# 5_High_V_Sensor.net
KiCad netlist of a schematic drawn in Altium Designer
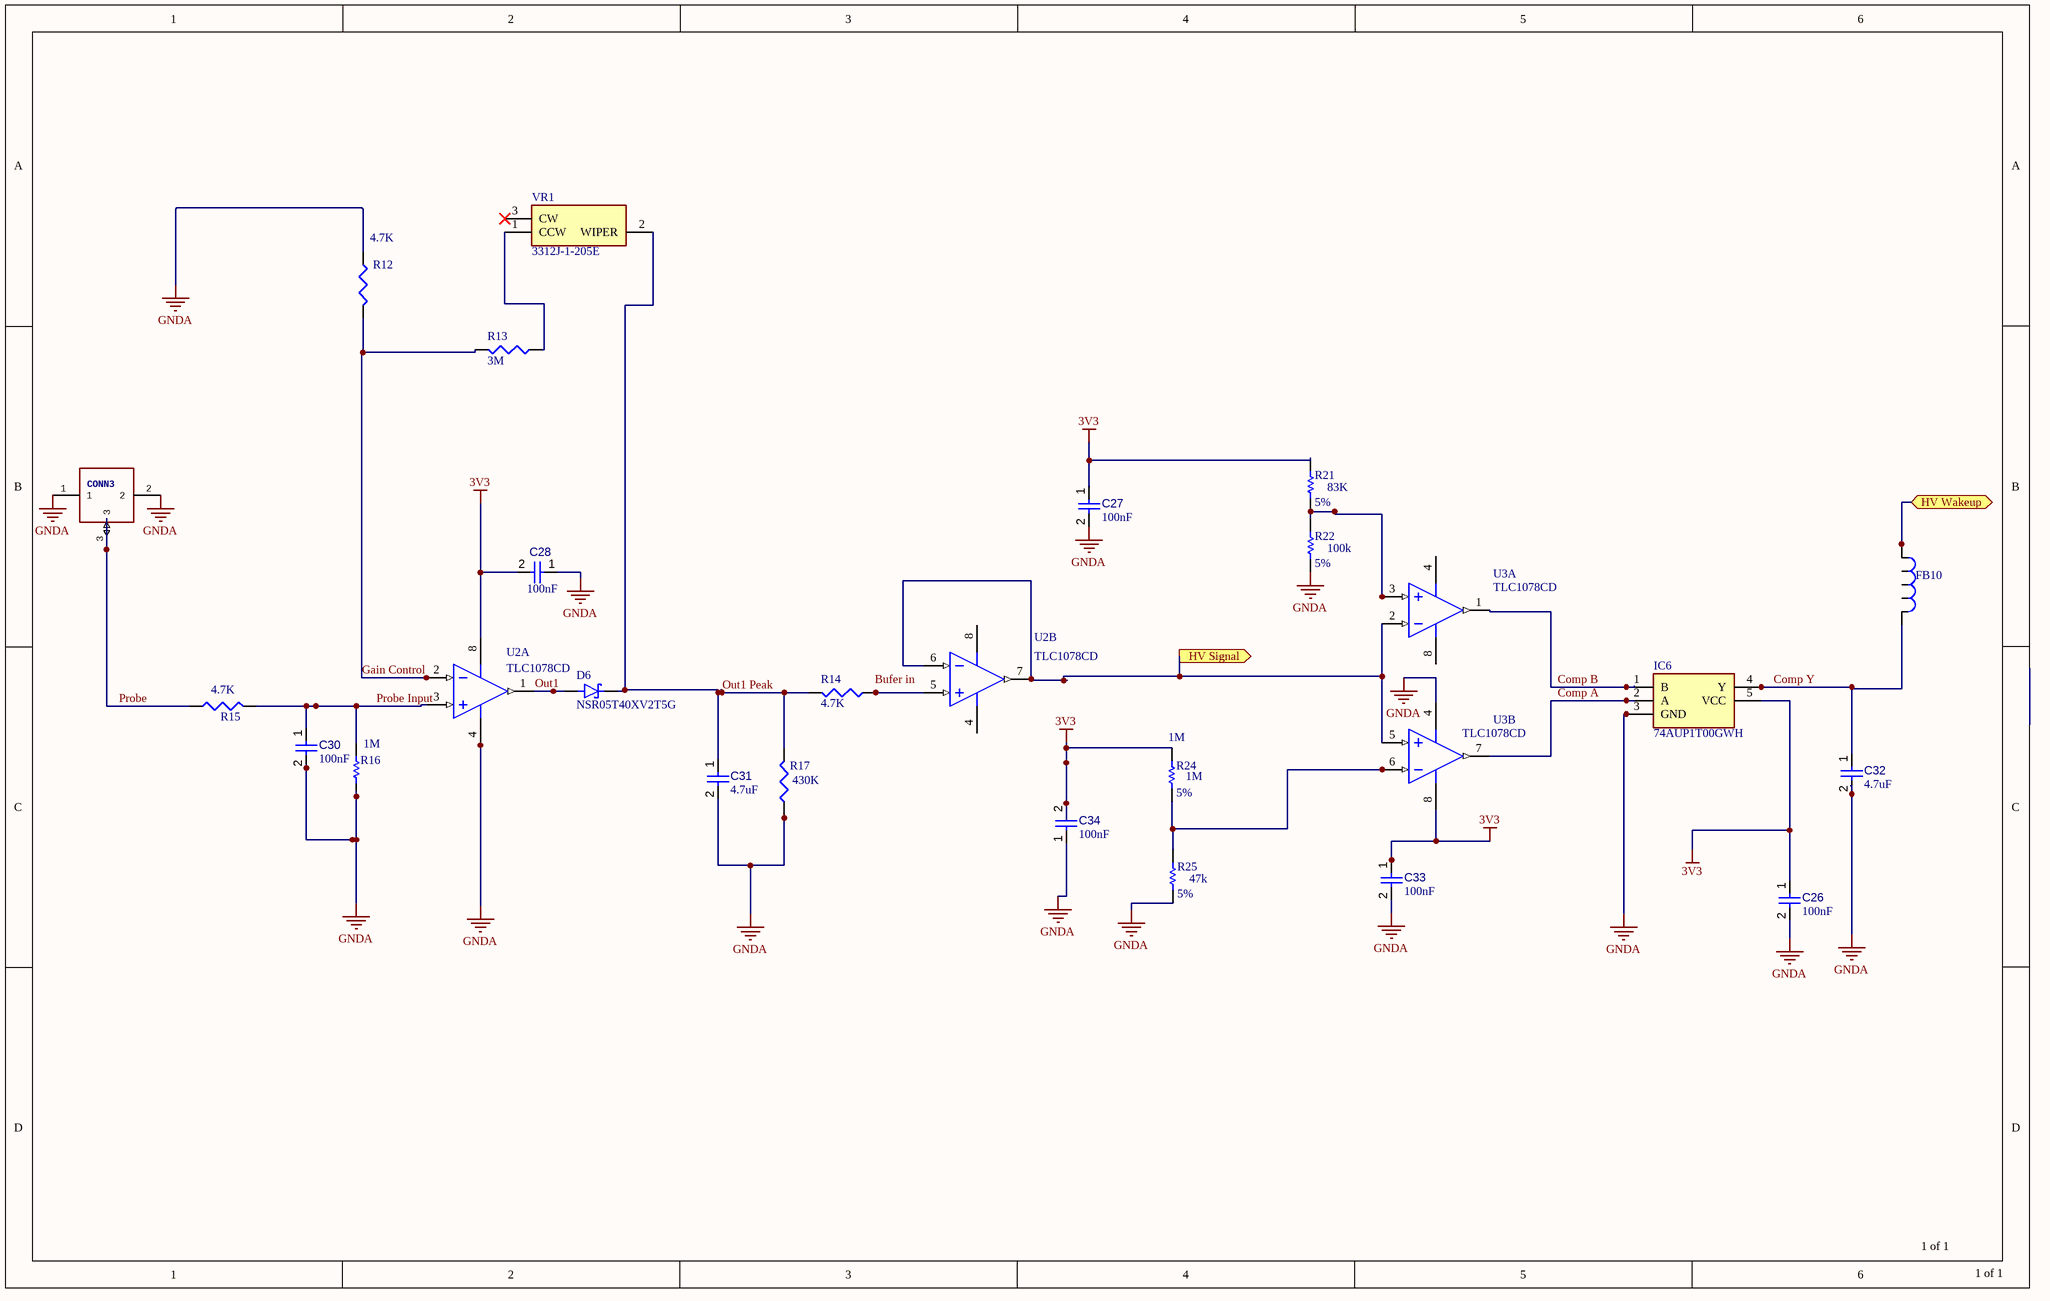
[diagram p0: [5]High_V_Sensor.SchDoc]

(export (version "E")
  (design (tool "Eeschema 10.0.6"))
  (components
    (comp (ref "C26")
      (value "100nF")
      (footprint "CAPC1608X90X40ML10T20")
      (description "Chip Capacitor, 100 nF, +/- 10%, 50 V, 0603 (1608 Metric)")
      (fields (field (name "TOLERANCE") "10%") (field (name "Comment") "Capacitor 100 nF +/-10% 50 V 0603"))
      (libsource (lib "Latium Technologies") (part "CAP-NP-2"))
    )
    (comp (ref "C27")
      (value "100nF")
      (footprint "CAPC1608X90X40ML10T20")
      (description "Chip Capacitor, 100 nF, +/- 10%, 50 V, 0603 (1608 Metric)")
      (fields (field (name "TOLERANCE") "10%") (field (name "Comment") "Capacitor 100 nF +/-10% 50 V 0603"))
      (libsource (lib "Latium Technologies") (part "CAP-NP-2"))
    )
    (comp (ref "C28")
      (value "100nF")
      (footprint "CAPC1608X90X40ML10T20")
      (description "Chip Capacitor, 100 nF, +/- 10%, 50 V, 0603 (1608 Metric)")
      (fields (field (name "TOLERANCE") "10%") (field (name "Comment") "Capacitor 100 nF +/-10% 50 V 0603"))
      (libsource (lib "Latium Technologies") (part "CAP-NP-2"))
    )
    (comp (ref "C30")
      (value "100nF")
      (footprint "CAPC1608X90X40ML10T20")
      (description "Chip Capacitor, 100 nF, +/- 10%, 50 V, 0603 (1608 Metric)")
      (fields (field (name "TOLERANCE") "10%") (field (name "Comment") "Capacitor 100 nF +/-10% 50 V 0603"))
      (libsource (lib "Latium Technologies") (part "CAP-NP-2"))
    )
    (comp (ref "C31")
      (value "4.7uF")
      (footprint "CAPC1608X90X40ML10T20")
      (description "Chip Capacitor, 4.7uF, +/- 10%, 50 V, 0603 (1608 Metric)")
      (fields (field (name "TOLERANCE") "10%"))
      (libsource (lib "Latium Technologies") (part "CAP-NP-2"))
    )
    (comp (ref "C32")
      (value "4.7uF")
      (footprint "CAPC1608X90X40ML10T20")
      (description "Chip Capacitor, 4.7uF, +/- 10%, 50 V, 0603 (1608 Metric)")
      (fields (field (name "TOLERANCE") "10%"))
      (libsource (lib "Latium Technologies") (part "CAP-NP-2"))
    )
    (comp (ref "C33")
      (value "100nF")
      (footprint "CAPC1608X90X40ML10T20")
      (description "Chip Capacitor, 100 nF, +/- 10%, 50 V, 0603 (1608 Metric)")
      (fields (field (name "TOLERANCE") "10%") (field (name "Comment") "Capacitor 100 nF +/-10% 50 V 0603"))
      (libsource (lib "Latium Technologies") (part "CAP-NP-2"))
    )
    (comp (ref "C34")
      (value "100nF")
      (footprint "CAPC1608X90X40ML10T20")
      (description "Chip Capacitor, 100 nF, +/- 10%, 50 V, 0603 (1608 Metric)")
      (fields (field (name "TOLERANCE") "10%") (field (name "Comment") "Capacitor 100 nF +/-10% 50 V 0603"))
      (libsource (lib "Latium Technologies") (part "CAP-NP-2"))
    )
    (comp (ref "CONN3")
      (value "U.FL-R-SMT-1")
      (footprint "U.FL-R-SMT-1")
      (fields (field (name "LIBRARYNAME") "Kris"))
      (libsource (lib "Schlib_For_High_Voltage_Sensor") (part "U.FL-R-SMT-1"))
    )
    (comp (ref "D6")
      (value "NSR05T40XV2T5G")
      (footprint "PcbLibForHigh_Voltage_Sensor:DIOM1006X40N")
      (description "Diode Schottky 30V 500mA (DC) Surface Mount SOD-923")
      (fields (field (name "MF") "ON Semiconductor") (field (name "MP") "NSR0530P2T5G"))
      (libsource (lib "Schlib_For_High_Voltage_Sensor") (part "NSR0530P2T5G"))
    )
    (comp (ref "FB10")
      (value "BLM18AG102SN1D")
      (footprint "Ferrite Bead")
      (description "Ferrite Bead 1KOhm @100MHz")
      (libsource (lib "MasterLib") (part "Ferrite Bead"))
    )
    (comp (ref "IC6")
      (value "74AUP1T00GWH")
      (footprint "SamacSys:SOT65P212X110-5N")
      (description "Integrated Circuit")
      (fields
        (field (name "MOUSER PART NUMBER") "771-74AUP1T87GWH")
        (field (name "ARROW PART NUMBER") "74AUP1T87GWH")
      )
      (libsource (lib "SamacSys") (part "74AUP1T87GWH"))
    )
    (comp (ref "R12")
      (value "4.7K")
      (footprint "RESC0603")
      (description "RESISTOR")
      (libsource (lib "HVLib") (part "RESISTOR"))
    )
    (comp (ref "R13")
      (value "3M")
      (footprint "RESC0603")
      (description "RESISTOR")
      (libsource (lib "HVLib") (part "RESISTOR"))
    )
    (comp (ref "R14")
      (value "4.7K")
      (footprint "RESC0603")
      (description "RESISTOR")
      (libsource (lib "HVLib") (part "RESISTOR"))
    )
    (comp (ref "R15")
      (value "4.7K")
      (footprint "RESC0603")
      (description "RESISTOR")
      (libsource (lib "HVLib") (part "RESISTOR"))
    )
    (comp (ref "R16")
      (value "1M")
      (footprint "RES 0603")
      (description "1M 1% 0.1W [0603]")
      (fields (field (name "TOLERANCE") "1%"))
      (libsource (lib "MasterLib") (part "RES 3.3M 1% 0.1W [0603]"))
    )
    (comp (ref "R17")
      (value "430K")
      (footprint "RESC0603")
      (description "RESISTOR")
      (libsource (lib "HVLib") (part "RESISTOR"))
    )
    (comp (ref "R21")
      (value "83K")
      (footprint "RES 0603")
      (description "RES 83.3K 1% 0.1W [0603]")
      (fields (field (name "TOLERANCE") "5%") (field (name "Comment") "83.3K"))
      (libsource (lib "MasterLib") (part "RES 3.3M 1% 0.1W [0603]"))
    )
    (comp (ref "R22")
      (value "100k")
      (footprint "RES 0603")
      (description "RES 100K 5% 0.1W [0603]")
      (fields (field (name "TOLERANCE") "5%"))
      (libsource (lib "MasterLib") (part "RES 3.3M 1% 0.1W [0603]"))
    )
    (comp (ref "R24")
      (value "1M")
      (footprint "RES 0603")
      (description "1M 1% 0.1W [0603]")
      (fields (field (name "ALTIUM_VALUE") "1M") (field (name "TOLERANCE") "5%"))
      (libsource (lib "MasterLib") (part "RES 3.3M 1% 0.1W [0603]"))
    )
    (comp (ref "R25")
      (value "47k")
      (footprint "RES 0603")
      (description "RES 47K 5% 0.1W [0603]")
      (fields (field (name "TOLERANCE") "5%"))
      (libsource (lib "MasterLib") (part "RES 3.3M 1% 0.1W [0603]"))
    )
    (comp (ref "U2")
      (value "TLC1078CD")
      (footprint "D0008A_N")
      (fields (field (name "MANUFACTURER") "Texas Instruments"))
      (libsource (lib "Schlib_For_High_Voltage_Sensor") (part "TLC1078"))
    )
    (comp (ref "U3")
      (value "TLC1078CD")
      (footprint "D0008A_N")
      (fields (field (name "MANUFACTURER") "Texas Instruments"))
      (libsource (lib "Schlib_For_High_Voltage_Sensor") (part "TLC1078"))
    )
    (comp (ref "VR1")
      (value "3312J-1-205E")
      (footprint "PcbLibForHigh_Voltage_Sensor:3312J1502E")
      (description "Variable Resistor, 2M Ohm")
      (fields
        (field (name "MANUFACTURER_PART_NUMBER") "3312J-1-205")
        (field (name "MOUSER PART NUMBER") "652-3312J-1-205E")
      )
      (libsource (lib "Schlib_For_High_Voltage_Sensor") (part "3312J-1-502E"))
    )
  )
  (nets
    (net (code "2") (name "/Comp A") (class "Default")
      (node (ref "IC6") (pin "2") (pinfunction "A_2") (pintype "passive"))
      (node (ref "U3") (pin "7") (pinfunction "OUT2_7") (pintype "output"))
    )
    (net (code "3") (name "/Comp B") (class "Default")
      (node (ref "IC6") (pin "1") (pinfunction "B_1") (pintype "passive"))
      (node (ref "U3") (pin "1") (pinfunction "OUT1_1") (pintype "output"))
    )
    (net (code "4") (name "/Comp Y") (class "Default")
      (node (ref "C32") (pin "1") (pinfunction "1_1") (pintype "passive"))
      (node (ref "FB10") (pin "2") (pinfunction "2_2") (pintype "passive"))
      (node (ref "IC6") (pin "4") (pinfunction "Y_4") (pintype "passive"))
    )
    (net (code "5") (name "/Gain Control") (class "Default")
      (node (ref "R12") (pin "2") (pintype "passive"))
      (node (ref "R13") (pin "2") (pintype "passive"))
      (node (ref "U2") (pin "2") (pinfunction "IN1-_2") (pintype "input"))
    )
    (net (code "6") (name "/HV Signal") (class "Default")
      (node (ref "U2") (pin "6") (pinfunction "IN2-_6") (pintype "input"))
      (node (ref "U2") (pin "7") (pinfunction "OUT2_7") (pintype "output"))
      (node (ref "U3") (pin "2") (pinfunction "IN1-_2") (pintype "input"))
      (node (ref "U3") (pin "5") (pinfunction "IN2+_5") (pintype "input"))
    )
    (net (code "7") (name "/HV Wakeup") (class "Default")
      (node (ref "FB10") (pin "1") (pinfunction "1_1") (pintype "passive"))
    )
    (net (code "8") (name "/Out1") (class "Default")
      (node (ref "D6") (pin "A") (pinfunction "A_A") (pintype "passive"))
      (node (ref "U2") (pin "1") (pinfunction "OUT1_1") (pintype "output"))
    )
    (net (code "9") (name "/Out1 Peak") (class "Default")
      (node (ref "C31") (pin "1") (pinfunction "1_1") (pintype "passive"))
      (node (ref "D6") (pin "C") (pinfunction "K_C") (pintype "passive"))
      (node (ref "R14") (pin "2") (pintype "passive"))
      (node (ref "R17") (pin "2") (pintype "passive"))
      (node (ref "VR1") (pin "2") (pinfunction "WIPER_2") (pintype "passive"))
    )
    (net (code "10") (name "/Probe") (class "Default")
      (node (ref "CONN3") (pin "3") (pinfunction "3_3") (pintype "bidirectional"))
      (node (ref "R15") (pin "1") (pintype "passive"))
    )
    (net (code "11") (name "/Probe Input") (class "Default")
      (node (ref "C30") (pin "1") (pinfunction "1_1") (pintype "passive"))
      (node (ref "R15") (pin "2") (pintype "passive"))
      (node (ref "R16") (pin "2") (pinfunction "2_2") (pintype "passive"))
      (node (ref "U2") (pin "3") (pinfunction "IN1+_3") (pintype "input"))
    )
    (net (code "12") (name "3V3") (class "Default")
      (node (ref "C26") (pin "1") (pinfunction "1_1") (pintype "passive"))
      (node (ref "C27") (pin "1") (pinfunction "1_1") (pintype "passive"))
      (node (ref "C28") (pin "2") (pinfunction "2_2") (pintype "passive"))
      (node (ref "C33") (pin "1") (pinfunction "1_1") (pintype "passive"))
      (node (ref "C34") (pin "2") (pinfunction "2_2") (pintype "passive"))
      (node (ref "IC6") (pin "5") (pinfunction "VCC_5") (pintype "passive"))
      (node (ref "R21") (pin "2") (pinfunction "2_2") (pintype "passive"))
      (node (ref "R24") (pin "2") (pinfunction "2_2") (pintype "passive"))
      (node (ref "U2") (pin "8") (pinfunction "VDD_8") (pintype "power_in"))
      (node (ref "U3") (pin "8") (pinfunction "VDD_8") (pintype "power_in"))
    )
    (net (code "13") (name "GNDA") (class "Default")
      (node (ref "C26") (pin "2") (pinfunction "2_2") (pintype "passive"))
      (node (ref "C27") (pin "2") (pinfunction "2_2") (pintype "passive"))
      (node (ref "C28") (pin "1") (pinfunction "1_1") (pintype "passive"))
      (node (ref "C30") (pin "2") (pinfunction "2_2") (pintype "passive"))
      (node (ref "C31") (pin "2") (pinfunction "2_2") (pintype "passive"))
      (node (ref "C32") (pin "2") (pinfunction "2_2") (pintype "passive"))
      (node (ref "C33") (pin "2") (pinfunction "2_2") (pintype "passive"))
      (node (ref "C34") (pin "1") (pinfunction "1_1") (pintype "passive"))
      (node (ref "CONN3") (pin "1") (pinfunction "1_1") (pintype "power_in"))
      (node (ref "CONN3") (pin "2") (pinfunction "2_2") (pintype "power_in"))
      (node (ref "IC6") (pin "3") (pinfunction "GND_3") (pintype "passive"))
      (node (ref "R12") (pin "1") (pintype "passive"))
      (node (ref "R16") (pin "1") (pinfunction "1_1") (pintype "passive"))
      (node (ref "R17") (pin "1") (pintype "passive"))
      (node (ref "R22") (pin "1") (pinfunction "1_1") (pintype "passive"))
      (node (ref "R25") (pin "1") (pinfunction "1_1") (pintype "passive"))
      (node (ref "U2") (pin "4") (pinfunction "GND_4") (pintype "power_in"))
      (node (ref "U3") (pin "4") (pinfunction "GND_4") (pintype "power_in"))
    )
    (net (code "14") (name "Net-(U2B-IN2+)") (class "Default")
      (node (ref "R14") (pin "1") (pintype "passive"))
      (node (ref "U2") (pin "5") (pinfunction "IN2+_5") (pintype "input"))
    )
    (net (code "15") (name "Net-(U3A-IN1+)") (class "Default")
      (node (ref "R21") (pin "1") (pinfunction "1_1") (pintype "passive"))
      (node (ref "R22") (pin "2") (pinfunction "2_2") (pintype "passive"))
      (node (ref "U3") (pin "3") (pinfunction "IN1+_3") (pintype "input"))
    )
    (net (code "16") (name "Net-(U3B-IN2-)") (class "Default")
      (node (ref "R24") (pin "1") (pinfunction "1_1") (pintype "passive"))
      (node (ref "R25") (pin "2") (pinfunction "2_2") (pintype "passive"))
      (node (ref "U3") (pin "6") (pinfunction "IN2-_6") (pintype "input"))
    )
    (net (code "17") (name "Net-(VR1-CCW)") (class "Default")
      (node (ref "R13") (pin "1") (pintype "passive"))
      (node (ref "VR1") (pin "1") (pinfunction "CCW_1") (pintype "passive"))
    )
    (net (code "18") (name "unconnected-(U2B-GND-Pad4)") (class "Default")
      (node (ref "U2") (pin "4") (pinfunction "GND_4") (pintype "power_in"))
    )
    (net (code "19") (name "unconnected-(U2B-VDD-Pad8)") (class "Default")
      (node (ref "U2") (pin "8") (pinfunction "VDD_8") (pintype "power_in"))
    )
    (net (code "20") (name "unconnected-(U3A-GND-Pad4)") (class "Default")
      (node (ref "U3") (pin "4") (pinfunction "GND_4") (pintype "power_in"))
    )
    (net (code "21") (name "unconnected-(U3A-VDD-Pad8)") (class "Default")
      (node (ref "U3") (pin "8") (pinfunction "VDD_8") (pintype "power_in"))
    )
    (net (code "22") (name "unconnected-(VR1-CW-Pad3)") (class "Default")
      (node (ref "VR1") (pin "3") (pinfunction "CW_3") (pintype "passive+no_connect"))
    )
  )
)
